# Sheet1.net
KiCad netlist of a schematic drawn in Altium Designer
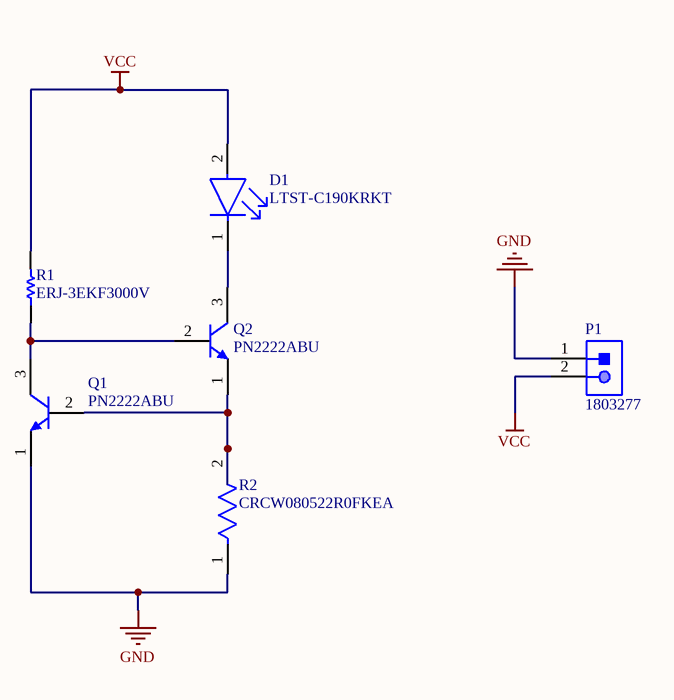
[diagram p0: Sheet1.SchDoc]

(export (version "E")
  (design (tool "Eeschema 10.0.6"))
  (components
    (comp (ref "D1")
      (value "LTST-C190KRKT")
      (footprint "FP-LTST-C190KRKT-MFG")
      (description "LED RED CLEAR CHIP SMD")
      (libsource (lib "Altium Content Vault") (part "8706943c75ba83719d021d2fdc84c58"))
    )
    (comp (ref "P1")
      (value "1803277")
      (footprint "PHOE-1803277_V")
      (description "Male Header, Pitch 3.81 mm, 1 x 2 Position, Height 7.25 mm, Tail Length 3.4 mm, RoHS, Bulk")
      (fields (field (name "MANUFACTURER") "Phoenix Contact"))
      (libsource (lib "Thomas Pickell") (part "CN-1P-M-R2"))
    )
    (comp (ref "Q1")
      (value "PN2222ABU")
      (footprint "FAIR-TO-92")
      (description "NPN General-Purpose Amplifier, 40 V, -55 to 150 degC, 3-Pin TO-92, RoHS, Bulk")
      (fields (field (name "POWER") "625mW") (field (name "MANUFACTURER") "Fairchild"))
      (libsource (lib "Thomas Pickell") (part "BJT-NPN-EBC-3"))
    )
    (comp (ref "Q2")
      (value "PN2222ABU")
      (footprint "FAIR-TO-92")
      (description "NPN General-Purpose Amplifier, 40 V, -55 to 150 degC, 3-Pin TO-92, RoHS, Bulk")
      (fields (field (name "POWER") "625mW") (field (name "MANUFACTURER") "Fairchild"))
      (libsource (lib "Thomas Pickell") (part "BJT-NPN-EBC-3"))
    )
    (comp (ref "R1")
      (value "ERJ-3EKF3000V")
      (footprint "RESC1608X55X30LL15T15")
      (fields (field (name "MANUFACTURER") "Panasonic"))
      (libsource (lib "Altium Content Vault") (part "RES"))
    )
    (comp (ref "R2")
      (value "CRCW080522R0FKEA")
      (footprint "FP-CRCW0805-e3-IPC_C")
      (description "RES Thick Film, 22Ω, 1%, 0.125W, 100ppm/°C, 0805")
      (fields (field (name "TOLERANCE") "1%"))
      (libsource (lib "Altium Content Vault") (part "1029c3af85768c4190bb7ad29bc67b5"))
    )
  )
  (nets
    (net (code "1") (name "GND") (class "Default")
      (node (ref "P1") (pin "1") (pinfunction "1_1") (pintype "passive"))
      (node (ref "Q1") (pin "1") (pinfunction "E_1") (pintype "passive"))
      (node (ref "R2") (pin "1") (pinfunction "1_1") (pintype "passive"))
    )
    (net (code "2") (name "Net-(D1-C)") (class "Default")
      (node (ref "D1") (pin "1") (pinfunction "C_1") (pintype "passive"))
      (node (ref "Q2") (pin "3") (pinfunction "C_3") (pintype "passive"))
    )
    (net (code "3") (name "Net-(Q1-B)") (class "Default")
      (node (ref "Q1") (pin "2") (pinfunction "B_2") (pintype "passive"))
      (node (ref "Q2") (pin "1") (pinfunction "E_1") (pintype "passive"))
      (node (ref "R2") (pin "2") (pinfunction "2_2") (pintype "passive"))
    )
    (net (code "4") (name "Net-(Q1-C)") (class "Default")
      (node (ref "Q1") (pin "3") (pinfunction "C_3") (pintype "passive"))
      (node (ref "Q2") (pin "2") (pinfunction "B_2") (pintype "passive"))
      (node (ref "R1") (pin "1") (pinfunction "1_1") (pintype "passive"))
    )
    (net (code "5") (name "VCC") (class "Default")
      (node (ref "D1") (pin "2") (pinfunction "A_2") (pintype "passive"))
      (node (ref "P1") (pin "2") (pinfunction "2_2") (pintype "passive"))
      (node (ref "R1") (pin "2") (pinfunction "2_2") (pintype "passive"))
    )
  )
)
